# STM32G473CET6_PINOUT.net
KiCad netlist of a schematic drawn in Altium Designer
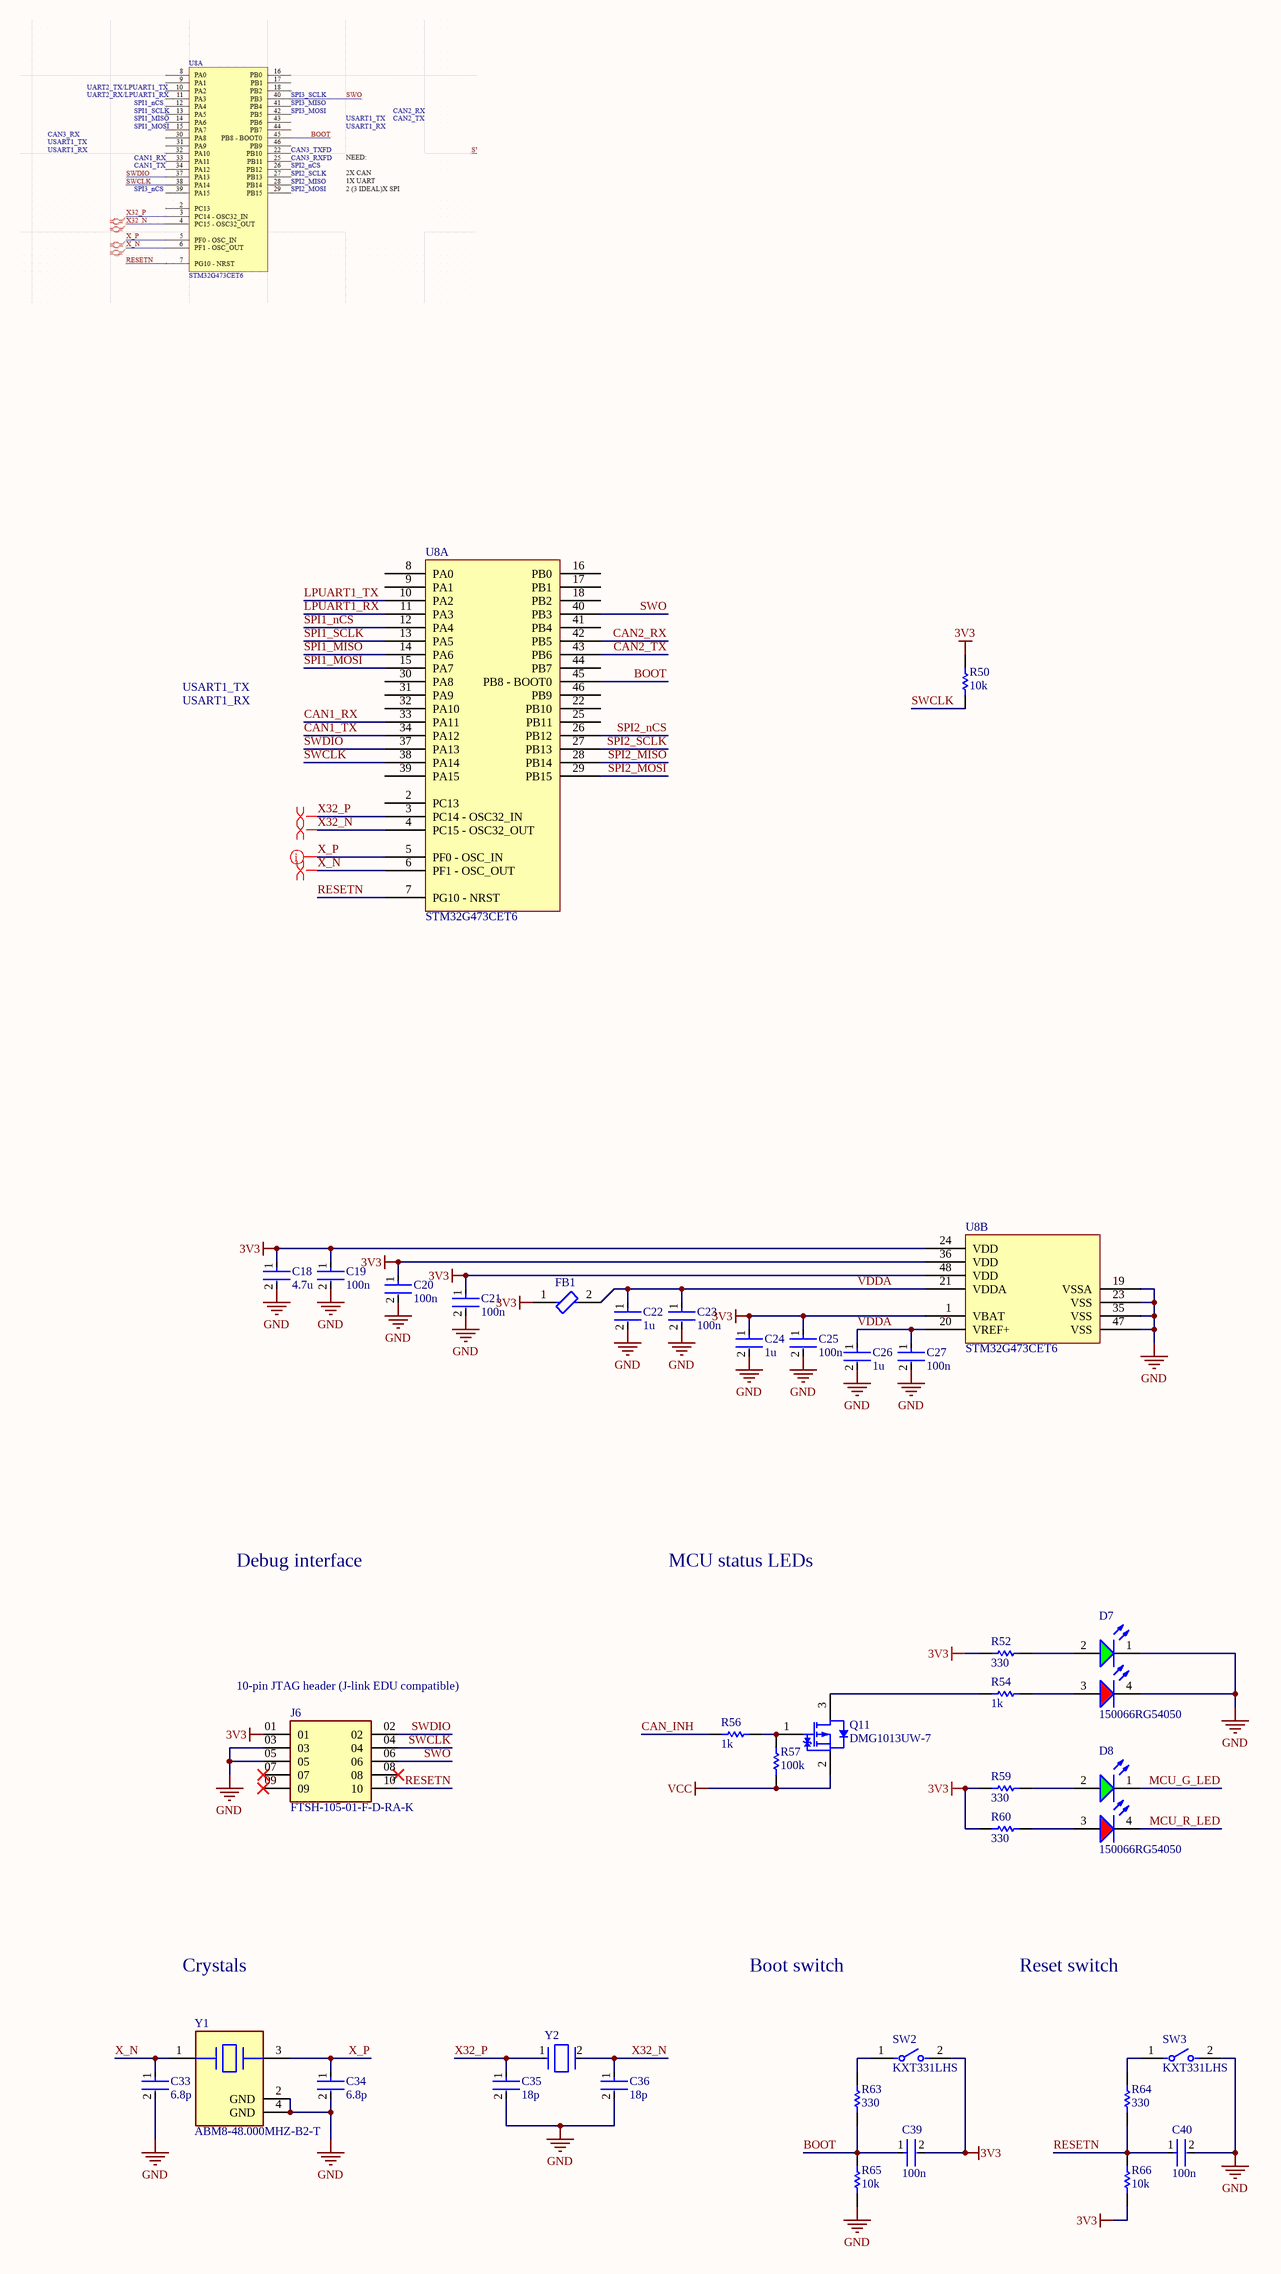
[diagram p0: STM32G473CET6_PINOUT.SchDoc]

(export (version "E")
  (design (tool "Eeschema 10.0.6"))
  (components
    (comp (ref "C18")
      (value "4.7u")
      (footprint "FP-0402-L_1_0_0_05-W_0_5-IPC_A")
      (description "LARGE PADS, 0402 CAP, CHANGE COMMENT TO MATCH REAL P/N")
      (libsource (lib "Space Concordia") (part "b4654b650e69147ec39a6b967a45e02"))
    )
    (comp (ref "C19")
      (value "100n")
      (footprint "FP-0402-L_1_0_0_05-W_0_5-IPC_A")
      (description "LARGE PADS, 0402 CAP, CHANGE COMMENT TO MATCH REAL P/N")
      (libsource (lib "Space Concordia") (part "b4654b650e69147ec39a6b967a45e02"))
    )
    (comp (ref "C20")
      (value "100n")
      (footprint "FP-0402-L_1_0_0_05-W_0_5-IPC_A")
      (description "LARGE PADS, 0402 CAP, CHANGE COMMENT TO MATCH REAL P/N")
      (libsource (lib "Space Concordia") (part "b4654b650e69147ec39a6b967a45e02"))
    )
    (comp (ref "C21")
      (value "100n")
      (footprint "FP-0402-L_1_0_0_05-W_0_5-IPC_A")
      (description "LARGE PADS, 0402 CAP, CHANGE COMMENT TO MATCH REAL P/N")
      (libsource (lib "Space Concordia") (part "b4654b650e69147ec39a6b967a45e02"))
    )
    (comp (ref "C22")
      (value "1u")
      (footprint "FP-0402-L_1_0_0_05-W_0_5-IPC_A")
      (description "LARGE PADS, 0402 CAP, CHANGE COMMENT TO MATCH REAL P/N")
      (libsource (lib "Space Concordia") (part "b4654b650e69147ec39a6b967a45e02"))
    )
    (comp (ref "C23")
      (value "100n")
      (footprint "FP-0402-L_1_0_0_05-W_0_5-IPC_A")
      (description "LARGE PADS, 0402 CAP, CHANGE COMMENT TO MATCH REAL P/N")
      (libsource (lib "Space Concordia") (part "b4654b650e69147ec39a6b967a45e02"))
    )
    (comp (ref "C24")
      (value "1u")
      (footprint "FP-0402-L_1_0_0_05-W_0_5-IPC_A")
      (description "LARGE PADS, 0402 CAP, CHANGE COMMENT TO MATCH REAL P/N")
      (libsource (lib "Space Concordia") (part "b4654b650e69147ec39a6b967a45e02"))
    )
    (comp (ref "C25")
      (value "100n")
      (footprint "FP-0402-L_1_0_0_05-W_0_5-IPC_A")
      (description "LARGE PADS, 0402 CAP, CHANGE COMMENT TO MATCH REAL P/N")
      (libsource (lib "Space Concordia") (part "b4654b650e69147ec39a6b967a45e02"))
    )
    (comp (ref "C26")
      (value "1u")
      (footprint "FP-0402-L_1_0_0_05-W_0_5-IPC_A")
      (description "LARGE PADS, 0402 CAP, CHANGE COMMENT TO MATCH REAL P/N")
      (libsource (lib "Space Concordia") (part "b4654b650e69147ec39a6b967a45e02"))
    )
    (comp (ref "C27")
      (value "100n")
      (footprint "FP-0402-L_1_0_0_05-W_0_5-IPC_A")
      (description "LARGE PADS, 0402 CAP, CHANGE COMMENT TO MATCH REAL P/N")
      (libsource (lib "Space Concordia") (part "b4654b650e69147ec39a6b967a45e02"))
    )
    (comp (ref "C33")
      (value "6.8p")
      (footprint "FP-0402-L_1_0_0_05-W_0_5-IPC_A")
      (description "LARGE PADS, 0402 CAP, CHANGE COMMENT TO MATCH REAL P/N")
      (libsource (lib "Space Concordia") (part "b4654b650e69147ec39a6b967a45e02"))
    )
    (comp (ref "C34")
      (value "6.8p")
      (footprint "FP-0402-L_1_0_0_05-W_0_5-IPC_A")
      (description "LARGE PADS, 0402 CAP, CHANGE COMMENT TO MATCH REAL P/N")
      (libsource (lib "Space Concordia") (part "b4654b650e69147ec39a6b967a45e02"))
    )
    (comp (ref "C35")
      (value "18p")
      (footprint "FP-0402-L_1_0_0_05-W_0_5-IPC_A")
      (description "LARGE PADS, 0402 CAP, CHANGE COMMENT TO MATCH REAL P/N")
      (libsource (lib "Space Concordia") (part "b4654b650e69147ec39a6b967a45e02"))
    )
    (comp (ref "C36")
      (value "18p")
      (footprint "FP-0402-L_1_0_0_05-W_0_5-IPC_A")
      (description "LARGE PADS, 0402 CAP, CHANGE COMMENT TO MATCH REAL P/N")
      (libsource (lib "Space Concordia") (part "b4654b650e69147ec39a6b967a45e02"))
    )
    (comp (ref "C39")
      (value "100n")
      (footprint "FP-0402-L_1_0_0_05-W_0_5-IPC_A")
      (description "LARGE PADS, 0402 CAP, CHANGE COMMENT TO MATCH REAL P/N")
      (libsource (lib "Space Concordia") (part "b4654b650e69147ec39a6b967a45e02"))
    )
    (comp (ref "C40")
      (value "100n")
      (footprint "FP-0402-L_1_0_0_05-W_0_5-IPC_A")
      (description "LARGE PADS, 0402 CAP, CHANGE COMMENT TO MATCH REAL P/N")
      (libsource (lib "Space Concordia") (part "b4654b650e69147ec39a6b967a45e02"))
    )
    (comp (ref "D7")
      (value "150066RG54050")
      (footprint "WL-SBCD_0606")
      (description "Led, Red/Grn, 180Mcd/230Mcd, 624Nm/525Nm Rohs Compliant: Yes")
      (fields (field (name "SOURCE") "rgled.SchLib"))
      (libsource (lib "Space Concordia") (part "CMP-004-00034-2"))
    )
    (comp (ref "D8")
      (value "150066RG54050")
      (footprint "WL-SBCD_0606")
      (description "Led, Red/Grn, 180Mcd/230Mcd, 624Nm/525Nm Rohs Compliant: Yes")
      (fields (field (name "SOURCE") "rgled.SchLib"))
      (libsource (lib "Space Concordia") (part "CMP-004-00034-2"))
    )
    (comp (ref "FB1")
      (value "BLM15PX601SN1D")
      (footprint "FP-BLM15-0_05-MFG")
      (description "Chip Ferrite Bead, 0402, 600Ω @ 100MHz, 0.23Ω, 25%, 900mA")
      (fields (field (name "TOLERANCE") "25%"))
      (libsource (lib "Altium Content Vault") (part "5f30dd21d616792df468990f7003faa"))
    )
    (comp (ref "J6")
      (value "FTSH-105-01-F-D-RA-K")
      (footprint "FTSH-105-01-F-D-RA-K-Footprint-1")
      (libsource (lib "Space Concordia") (part "FTSH-105-01-F-D-RA-K-Symbol-1"))
    )
    (comp (ref "Q11")
      (value "DMG1013UW-7")
      (footprint "DIOD-SOT323-3_V")
      (fields (field (name "MANUFACTURER") "Diodes Inc"))
      (libsource (lib "Altium Content Vault") (part "PEMOS-GSD-3_C"))
    )
    (comp (ref "R50")
      (value "10k")
      (footprint "R0603B")
      (description "Resistor")
      (libsource (lib "Space Concordia") (part "Resistor"))
    )
    (comp (ref "R52")
      (value "330")
      (footprint "R0603B")
      (description "Resistor")
      (libsource (lib "Space Concordia") (part "Resistor"))
    )
    (comp (ref "R54")
      (value "1k")
      (footprint "R0603B")
      (description "Resistor")
      (libsource (lib "Space Concordia") (part "Resistor"))
    )
    (comp (ref "R56")
      (value "1k")
      (footprint "R0603B")
      (description "Resistor")
      (libsource (lib "Space Concordia") (part "Resistor"))
    )
    (comp (ref "R57")
      (value "100k")
      (footprint "R0603B")
      (description "Resistor")
      (libsource (lib "Space Concordia") (part "Resistor"))
    )
    (comp (ref "R59")
      (value "330")
      (footprint "R0603B")
      (description "Resistor")
      (libsource (lib "Space Concordia") (part "Resistor"))
    )
    (comp (ref "R60")
      (value "330")
      (footprint "R0603B")
      (description "Resistor")
      (libsource (lib "Space Concordia") (part "Resistor"))
    )
    (comp (ref "R63")
      (value "330")
      (footprint "R0603B")
      (description "Resistor")
      (libsource (lib "Space Concordia") (part "Resistor"))
    )
    (comp (ref "R64")
      (value "330")
      (footprint "R0603B")
      (description "Resistor")
      (libsource (lib "Space Concordia") (part "Resistor"))
    )
    (comp (ref "R65")
      (value "10k")
      (footprint "R0603B")
      (description "Resistor")
      (libsource (lib "Space Concordia") (part "Resistor"))
    )
    (comp (ref "R66")
      (value "10k")
      (footprint "R0603B")
      (description "Resistor")
      (libsource (lib "Space Concordia") (part "Resistor"))
    )
    (comp (ref "SW2")
      (value "KXT331LHS")
      (footprint "FP-KXT331LHS-MFG")
      (description "SWITCH TACTILE SPST-NO 0.02A 15V")
      (libsource (lib "Altium Content Vault") (part "bb27bde45df87f1f469753f287ef5ae"))
    )
    (comp (ref "SW3")
      (value "KXT331LHS")
      (footprint "FP-KXT331LHS-MFG")
      (description "SWITCH TACTILE SPST-NO 0.02A 15V")
      (libsource (lib "Altium Content Vault") (part "bb27bde45df87f1f469753f287ef5ae"))
    )
    (comp (ref "U8")
      (value "STM32G473CET6")
      (footprint "TSQFP50P900X900X160-48N")
      (description "RISC Microcontroller, 32-Bit, 170MHz")
      (libsource (lib "Space Concordia") (part "STM32G473CET6"))
    )
    (comp (ref "Y1")
      (value "ABM8-48.000MHZ-B2-T")
      (footprint "FP-ABM8-MFG")
      (description "Crystal 48MHz ±20ppm 18pF SMD-4 3.2mm x 2.5mm")
      (fields (field (name "TOLERANCE") "20ppm"))
      (libsource (lib "Altium Content Vault") (part "dfdb7f9a12507849fb681da9a70121c"))
    )
    (comp (ref "Y2")
      (value "ECS-.327-12.5-1210-TR")
      (footprint "FP-ECX-1210-MFG")
      (description "CRYSTAL 32.7680KHZ 12.5PF SMD")
      (fields
        (field (name "OCTOPART") "https://octopart.com/ecs-.327-12.5-1210-tr-ecs+international-81221340")
        (field (name "TOLERANCE") "20ppm")
      )
      (libsource (lib "Altium Content Vault") (part "99724985039315a44fd0d1401b84e49"))
    )
  )
  (nets
    (net (code "1") (name "/BOOT") (class "Default")
      (node (ref "C39") (pin "1") (pinfunction "1_1") (pintype "passive"))
      (node (ref "R63") (pin "1") (pinfunction "1_1") (pintype "passive"))
      (node (ref "R65") (pin "2") (pinfunction "2_2") (pintype "passive"))
      (node (ref "U8") (pin "45") (pinfunction "PB8_-_BOOT0_45") (pintype "passive"))
    )
    (net (code "2") (name "/CAN1_RX") (class "Default")
      (node (ref "U8") (pin "33") (pinfunction "PA11_33") (pintype "passive"))
    )
    (net (code "3") (name "/CAN1_TX") (class "Default")
      (node (ref "U8") (pin "34") (pinfunction "PA12_34") (pintype "passive"))
    )
    (net (code "4") (name "/CAN2_RX") (class "Default")
      (node (ref "U8") (pin "42") (pinfunction "PB5_42") (pintype "passive"))
    )
    (net (code "5") (name "/CAN2_TX") (class "Default")
      (node (ref "U8") (pin "43") (pinfunction "PB6_43") (pintype "passive"))
    )
    (net (code "6") (name "/CAN_INH") (class "Default")
      (node (ref "R56") (pin "2") (pinfunction "2_2") (pintype "passive"))
    )
    (net (code "7") (name "/LPUART1_RX") (class "Default")
      (node (ref "U8") (pin "11") (pinfunction "PA3_11") (pintype "passive"))
    )
    (net (code "8") (name "/LPUART1_TX") (class "Default")
      (node (ref "U8") (pin "10") (pinfunction "PA2_10") (pintype "passive"))
    )
    (net (code "9") (name "/MCU_G_LED") (class "Default")
      (node (ref "D8") (pin "1") (pinfunction "K_1") (pintype "passive"))
    )
    (net (code "10") (name "/MCU_R_LED") (class "Default")
      (node (ref "D8") (pin "4") (pinfunction "K_4") (pintype "passive"))
    )
    (net (code "11") (name "/RESETN") (class "Default")
      (node (ref "C40") (pin "1") (pinfunction "1_1") (pintype "passive"))
      (node (ref "J6") (pin "10") (pinfunction "10_10") (pintype "passive"))
      (node (ref "R64") (pin "1") (pinfunction "1_1") (pintype "passive"))
      (node (ref "R66") (pin "2") (pinfunction "2_2") (pintype "passive"))
      (node (ref "U8") (pin "7") (pinfunction "PG10_-_NRST_7") (pintype "passive"))
    )
    (net (code "12") (name "/SPI1_MISO") (class "Default")
      (node (ref "U8") (pin "14") (pinfunction "PA6_14") (pintype "passive"))
    )
    (net (code "13") (name "/SPI1_MOSI") (class "Default")
      (node (ref "U8") (pin "15") (pinfunction "PA7_15") (pintype "passive"))
    )
    (net (code "14") (name "/SPI1_SCLK") (class "Default")
      (node (ref "U8") (pin "13") (pinfunction "PA5_13") (pintype "passive"))
    )
    (net (code "15") (name "/SPI1_nCS") (class "Default")
      (node (ref "U8") (pin "12") (pinfunction "PA4_12") (pintype "passive"))
    )
    (net (code "16") (name "/SPI2_MISO") (class "Default")
      (node (ref "U8") (pin "28") (pinfunction "PB14_28") (pintype "passive"))
    )
    (net (code "17") (name "/SPI2_MOSI") (class "Default")
      (node (ref "U8") (pin "29") (pinfunction "PB15_29") (pintype "passive"))
    )
    (net (code "18") (name "/SPI2_SCLK") (class "Default")
      (node (ref "U8") (pin "27") (pinfunction "PB13_27") (pintype "passive"))
    )
    (net (code "19") (name "/SPI2_nCS") (class "Default")
      (node (ref "U8") (pin "26") (pinfunction "PB12_26") (pintype "passive"))
    )
    (net (code "20") (name "/SWCLK") (class "Default")
      (node (ref "J6") (pin "04") (pinfunction "04_04") (pintype "passive"))
      (node (ref "R50") (pin "1") (pinfunction "1_1") (pintype "passive"))
      (node (ref "U8") (pin "38") (pinfunction "PA14_38") (pintype "passive"))
    )
    (net (code "21") (name "/SWDIO") (class "Default")
      (node (ref "J6") (pin "02") (pinfunction "02_02") (pintype "passive"))
      (node (ref "U8") (pin "37") (pinfunction "PA13_37") (pintype "passive"))
    )
    (net (code "22") (name "/SWO") (class "Default")
      (node (ref "J6") (pin "06") (pinfunction "06_06") (pintype "passive"))
      (node (ref "U8") (pin "40") (pinfunction "PB3_40") (pintype "passive"))
    )
    (net (code "23") (name "/VDDA") (class "Default")
      (node (ref "C22") (pin "1") (pinfunction "1_1") (pintype "passive"))
      (node (ref "C23") (pin "1") (pinfunction "1_1") (pintype "passive"))
      (node (ref "C26") (pin "1") (pinfunction "1_1") (pintype "passive"))
      (node (ref "C27") (pin "1") (pinfunction "1_1") (pintype "passive"))
      (node (ref "FB1") (pin "2") (pinfunction "2_2") (pintype "passive"))
      (node (ref "U8") (pin "20") (pinfunction "VREF+_20") (pintype "passive"))
      (node (ref "U8") (pin "21") (pinfunction "VDDA_21") (pintype "passive"))
    )
    (net (code "24") (name "/X32_N") (class "Default")
      (node (ref "C36") (pin "1") (pinfunction "1_1") (pintype "passive"))
      (node (ref "U8") (pin "4") (pinfunction "PC15_-_OSC32_OUT_4") (pintype "passive"))
      (node (ref "Y2") (pin "2") (pinfunction "Out/In_2") (pintype "passive"))
    )
    (net (code "25") (name "/X32_P") (class "Default")
      (node (ref "C35") (pin "1") (pinfunction "1_1") (pintype "passive"))
      (node (ref "U8") (pin "3") (pinfunction "PC14_-_OSC32_IN_3") (pintype "passive"))
      (node (ref "Y2") (pin "1") (pinfunction "In/Out_1") (pintype "passive"))
    )
    (net (code "26") (name "/X_N") (class "Default")
      (node (ref "C33") (pin "1") (pinfunction "1_1") (pintype "passive"))
      (node (ref "U8") (pin "6") (pinfunction "PF1_-_OSC_OUT_6") (pintype "passive"))
      (node (ref "Y1") (pin "1") (pinfunction "1_1") (pintype "passive"))
    )
    (net (code "27") (name "/X_P") (class "Default")
      (node (ref "C34") (pin "1") (pinfunction "1_1") (pintype "passive"))
      (node (ref "U8") (pin "5") (pinfunction "PF0_-_OSC_IN_5") (pintype "passive"))
      (node (ref "Y1") (pin "3") (pinfunction "3_3") (pintype "passive"))
    )
    (net (code "28") (name "3V3") (class "Default")
      (node (ref "C18") (pin "1") (pinfunction "1_1") (pintype "passive"))
      (node (ref "C19") (pin "1") (pinfunction "1_1") (pintype "passive"))
      (node (ref "C20") (pin "1") (pinfunction "1_1") (pintype "passive"))
      (node (ref "C21") (pin "1") (pinfunction "1_1") (pintype "passive"))
      (node (ref "C24") (pin "1") (pinfunction "1_1") (pintype "passive"))
      (node (ref "C25") (pin "1") (pinfunction "1_1") (pintype "passive"))
      (node (ref "C39") (pin "2") (pinfunction "2_2") (pintype "passive"))
      (node (ref "FB1") (pin "1") (pinfunction "1_1") (pintype "passive"))
      (node (ref "J6") (pin "01") (pinfunction "01_01") (pintype "passive"))
      (node (ref "R50") (pin "2") (pinfunction "2_2") (pintype "passive"))
      (node (ref "R52") (pin "2") (pinfunction "2_2") (pintype "passive"))
      (node (ref "R59") (pin "2") (pinfunction "2_2") (pintype "passive"))
      (node (ref "R60") (pin "2") (pinfunction "2_2") (pintype "passive"))
      (node (ref "R66") (pin "1") (pinfunction "1_1") (pintype "passive"))
      (node (ref "SW2") (pin "2") (pinfunction "2_2") (pintype "passive"))
      (node (ref "U8") (pin "1") (pinfunction "VBAT_1") (pintype "passive"))
      (node (ref "U8") (pin "24") (pinfunction "VDD_24") (pintype "passive"))
      (node (ref "U8") (pin "36") (pinfunction "VDD_36") (pintype "passive"))
      (node (ref "U8") (pin "48") (pinfunction "VDD_48") (pintype "passive"))
    )
    (net (code "29") (name "GND") (class "Default")
      (node (ref "C18") (pin "2") (pinfunction "2_2") (pintype "passive"))
      (node (ref "C19") (pin "2") (pinfunction "2_2") (pintype "passive"))
      (node (ref "C20") (pin "2") (pinfunction "2_2") (pintype "passive"))
      (node (ref "C21") (pin "2") (pinfunction "2_2") (pintype "passive"))
      (node (ref "C22") (pin "2") (pinfunction "2_2") (pintype "passive"))
      (node (ref "C23") (pin "2") (pinfunction "2_2") (pintype "passive"))
      (node (ref "C24") (pin "2") (pinfunction "2_2") (pintype "passive"))
      (node (ref "C25") (pin "2") (pinfunction "2_2") (pintype "passive"))
      (node (ref "C26") (pin "2") (pinfunction "2_2") (pintype "passive"))
      (node (ref "C27") (pin "2") (pinfunction "2_2") (pintype "passive"))
      (node (ref "C33") (pin "2") (pinfunction "2_2") (pintype "passive"))
      (node (ref "C34") (pin "2") (pinfunction "2_2") (pintype "passive"))
      (node (ref "C35") (pin "2") (pinfunction "2_2") (pintype "passive"))
      (node (ref "C36") (pin "2") (pinfunction "2_2") (pintype "passive"))
      (node (ref "C40") (pin "2") (pinfunction "2_2") (pintype "passive"))
      (node (ref "D7") (pin "1") (pinfunction "K_1") (pintype "passive"))
      (node (ref "D7") (pin "4") (pinfunction "K_4") (pintype "passive"))
      (node (ref "J6") (pin "03") (pinfunction "03_03") (pintype "passive"))
      (node (ref "J6") (pin "05") (pinfunction "05_05") (pintype "passive"))
      (node (ref "R65") (pin "1") (pinfunction "1_1") (pintype "passive"))
      (node (ref "SW3") (pin "2") (pinfunction "2_2") (pintype "passive"))
      (node (ref "U8") (pin "19") (pinfunction "VSSA_19") (pintype "passive"))
      (node (ref "U8") (pin "23") (pinfunction "VSS_23") (pintype "passive"))
      (node (ref "U8") (pin "35") (pinfunction "VSS_35") (pintype "passive"))
      (node (ref "U8") (pin "47") (pinfunction "VSS_47") (pintype "passive"))
      (node (ref "Y1") (pin "2") (pinfunction "GND_2") (pintype "power_in"))
      (node (ref "Y1") (pin "4") (pinfunction "GND_4") (pintype "power_in"))
    )
    (net (code "30") (name "Net-(D7-A-Pad2)") (class "Default")
      (node (ref "D7") (pin "2") (pinfunction "A_2") (pintype "passive"))
      (node (ref "R52") (pin "1") (pinfunction "1_1") (pintype "passive"))
    )
    (net (code "31") (name "Net-(D7-A-Pad3)") (class "Default")
      (node (ref "D7") (pin "3") (pinfunction "A_3") (pintype "passive"))
      (node (ref "R54") (pin "1") (pinfunction "1_1") (pintype "passive"))
    )
    (net (code "32") (name "Net-(D8-A-Pad2)") (class "Default")
      (node (ref "D8") (pin "2") (pinfunction "A_2") (pintype "passive"))
      (node (ref "R59") (pin "1") (pinfunction "1_1") (pintype "passive"))
    )
    (net (code "33") (name "Net-(D8-A-Pad3)") (class "Default")
      (node (ref "D8") (pin "3") (pinfunction "A_3") (pintype "passive"))
      (node (ref "R60") (pin "1") (pinfunction "1_1") (pintype "passive"))
    )
    (net (code "34") (name "Net-(Q11-D)") (class "Default")
      (node (ref "Q11") (pin "3") (pinfunction "D_3") (pintype "passive"))
      (node (ref "R54") (pin "2") (pinfunction "2_2") (pintype "passive"))
    )
    (net (code "35") (name "Net-(Q11-G)") (class "Default")
      (node (ref "Q11") (pin "1") (pinfunction "G_1") (pintype "passive"))
      (node (ref "R56") (pin "1") (pinfunction "1_1") (pintype "passive"))
      (node (ref "R57") (pin "1") (pinfunction "1_1") (pintype "passive"))
    )
    (net (code "36") (name "Net-(R63-Pad2)") (class "Default")
      (node (ref "R63") (pin "2") (pinfunction "2_2") (pintype "passive"))
      (node (ref "SW2") (pin "1") (pinfunction "1_1") (pintype "passive"))
    )
    (net (code "37") (name "Net-(R64-Pad2)") (class "Default")
      (node (ref "R64") (pin "2") (pinfunction "2_2") (pintype "passive"))
      (node (ref "SW3") (pin "1") (pinfunction "1_1") (pintype "passive"))
    )
    (net (code "38") (name "VCC") (class "Default")
      (node (ref "Q11") (pin "2") (pinfunction "S_2") (pintype "passive"))
      (node (ref "R57") (pin "2") (pinfunction "2_2") (pintype "passive"))
    )
    (net (code "39") (name "unconnected-(J6-Pad07)") (class "Default")
      (node (ref "J6") (pin "07") (pinfunction "07_07") (pintype "passive+no_connect"))
    )
    (net (code "40") (name "unconnected-(J6-Pad08)") (class "Default")
      (node (ref "J6") (pin "08") (pinfunction "08_08") (pintype "passive+no_connect"))
    )
    (net (code "41") (name "unconnected-(J6-Pad09)") (class "Default")
      (node (ref "J6") (pin "09") (pinfunction "09_09") (pintype "passive+no_connect"))
    )
    (net (code "42") (name "unconnected-(U8A-PA0-Pad8)") (class "Default")
      (node (ref "U8") (pin "8") (pinfunction "PA0_8") (pintype "passive"))
    )
    (net (code "43") (name "unconnected-(U8A-PA1-Pad9)") (class "Default")
      (node (ref "U8") (pin "9") (pinfunction "PA1_9") (pintype "passive"))
    )
    (net (code "44") (name "unconnected-(U8A-PA8-Pad30)") (class "Default")
      (node (ref "U8") (pin "30") (pinfunction "PA8_30") (pintype "passive"))
    )
    (net (code "45") (name "unconnected-(U8A-PA9-Pad31)") (class "Default")
      (node (ref "U8") (pin "31") (pinfunction "PA9_31") (pintype "passive"))
    )
    (net (code "46") (name "unconnected-(U8A-PA10-Pad32)") (class "Default")
      (node (ref "U8") (pin "32") (pinfunction "PA10_32") (pintype "passive"))
    )
    (net (code "47") (name "unconnected-(U8A-PA15-Pad39)") (class "Default")
      (node (ref "U8") (pin "39") (pinfunction "PA15_39") (pintype "passive"))
    )
    (net (code "48") (name "unconnected-(U8A-PB0-Pad16)") (class "Default")
      (node (ref "U8") (pin "16") (pinfunction "PB0_16") (pintype "passive"))
    )
    (net (code "49") (name "unconnected-(U8A-PB1-Pad17)") (class "Default")
      (node (ref "U8") (pin "17") (pinfunction "PB1_17") (pintype "passive"))
    )
    (net (code "50") (name "unconnected-(U8A-PB2-Pad18)") (class "Default")
      (node (ref "U8") (pin "18") (pinfunction "PB2_18") (pintype "passive"))
    )
    (net (code "51") (name "unconnected-(U8A-PB4-Pad41)") (class "Default")
      (node (ref "U8") (pin "41") (pinfunction "PB4_41") (pintype "passive"))
    )
    (net (code "52") (name "unconnected-(U8A-PB7-Pad44)") (class "Default")
      (node (ref "U8") (pin "44") (pinfunction "PB7_44") (pintype "passive"))
    )
    (net (code "53") (name "unconnected-(U8A-PB9-Pad46)") (class "Default")
      (node (ref "U8") (pin "46") (pinfunction "PB9_46") (pintype "passive"))
    )
    (net (code "54") (name "unconnected-(U8A-PB10-Pad22)") (class "Default")
      (node (ref "U8") (pin "22") (pinfunction "PB10_22") (pintype "passive"))
    )
    (net (code "55") (name "unconnected-(U8A-PB11-Pad25)") (class "Default")
      (node (ref "U8") (pin "25") (pinfunction "PB11_25") (pintype "passive"))
    )
    (net (code "56") (name "unconnected-(U8A-PC13-Pad2)") (class "Default")
      (node (ref "U8") (pin "2") (pinfunction "PC13_2") (pintype "passive"))
    )
  )
)
